# motor-driver.net
KiCad netlist of a schematic drawn in EAGLE
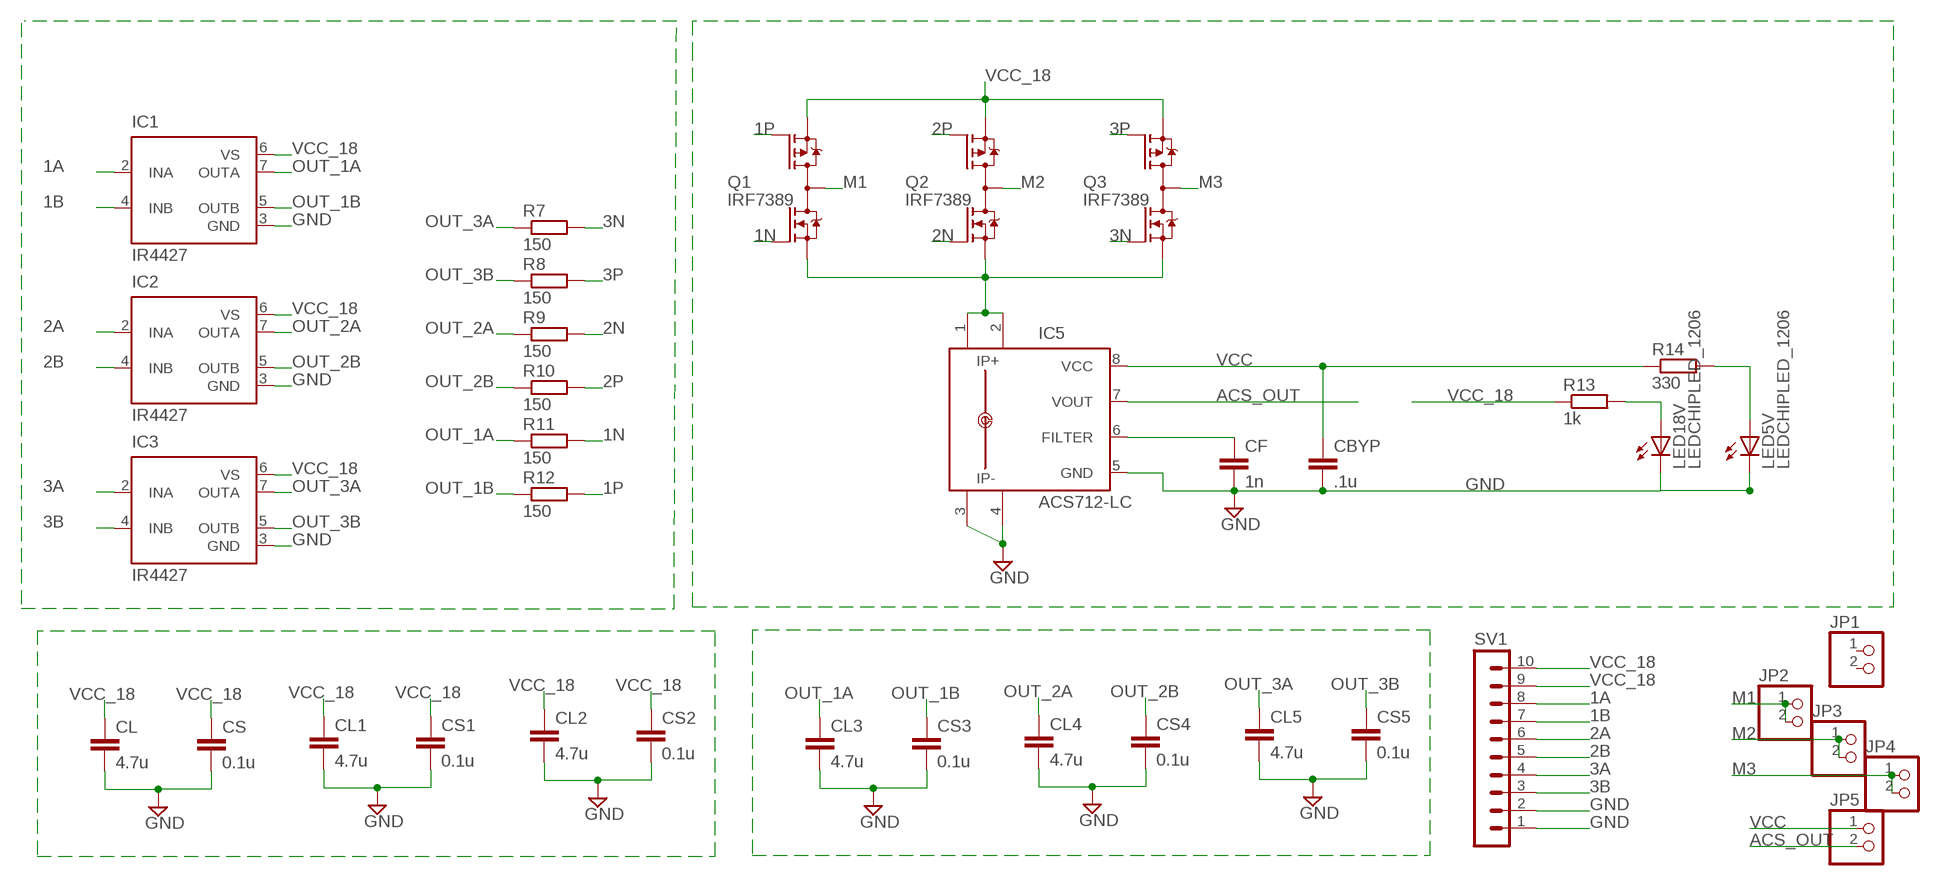
[diagram p0: schematic, sheet 1]

(export (version "E")
  (design (tool "Eeschema 10.0.6"))
  (components
    (comp (ref "CBYP")
      (value ".1u")
      (footprint "eagle-import:C1206")
      (libsource (lib "eagle-import") (part "CC1206"))
    )
    (comp (ref "CF")
      (value "1n")
      (footprint "eagle-import:C1206")
      (libsource (lib "eagle-import") (part "CC1206"))
    )
    (comp (ref "CL")
      (value "4.7u")
      (footprint "eagle-import:C1206")
      (libsource (lib "eagle-import") (part "CC1206"))
    )
    (comp (ref "CL1")
      (value "4.7u")
      (footprint "eagle-import:C1206")
      (libsource (lib "eagle-import") (part "CC1206"))
    )
    (comp (ref "CL2")
      (value "4.7u")
      (footprint "eagle-import:C1206")
      (libsource (lib "eagle-import") (part "CC1206"))
    )
    (comp (ref "CL3")
      (value "4.7u")
      (footprint "eagle-import:C1206")
      (libsource (lib "eagle-import") (part "CC1206"))
    )
    (comp (ref "CL4")
      (value "4.7u")
      (footprint "eagle-import:C1206")
      (libsource (lib "eagle-import") (part "CC1206"))
    )
    (comp (ref "CL5")
      (value "4.7u")
      (footprint "eagle-import:C1206")
      (libsource (lib "eagle-import") (part "CC1206"))
    )
    (comp (ref "CS")
      (value "0.1u")
      (footprint "eagle-import:C1206")
      (libsource (lib "eagle-import") (part "CC1206"))
    )
    (comp (ref "CS1")
      (value "0.1u")
      (footprint "eagle-import:C1206")
      (libsource (lib "eagle-import") (part "CC1206"))
    )
    (comp (ref "CS2")
      (value "0.1u")
      (footprint "eagle-import:C1206")
      (libsource (lib "eagle-import") (part "CC1206"))
    )
    (comp (ref "CS3")
      (value "0.1u")
      (footprint "eagle-import:C1206")
      (libsource (lib "eagle-import") (part "CC1206"))
    )
    (comp (ref "CS4")
      (value "0.1u")
      (footprint "eagle-import:C1206")
      (libsource (lib "eagle-import") (part "CC1206"))
    )
    (comp (ref "CS5")
      (value "0.1u")
      (footprint "eagle-import:C1206")
      (libsource (lib "eagle-import") (part "CC1206"))
    )
    (comp (ref "IC1")
      (value "IR4427")
      (footprint "eagle-import:DIL08")
      (fields (field (name "MF") "INTERNATIONAL RECTIFIER(IR)"))
      (libsource (lib "eagle-import") (part "IR4427"))
    )
    (comp (ref "IC2")
      (value "IR4427")
      (footprint "eagle-import:DIL08")
      (fields (field (name "MF") "INTERNATIONAL RECTIFIER(IR)"))
      (libsource (lib "eagle-import") (part "IR4427"))
    )
    (comp (ref "IC3")
      (value "IR4427")
      (footprint "eagle-import:DIL08")
      (fields (field (name "MF") "INTERNATIONAL RECTIFIER(IR)"))
      (libsource (lib "eagle-import") (part "IR4427"))
    )
    (comp (ref "IC5")
      (value "ACS712-LC")
      (footprint "eagle-import:SOIC8")
      (libsource (lib "eagle-import") (part "ACS712-LC"))
    )
    (comp (ref "JP1")
      (value "PINHD-1X2")
      (footprint "eagle-import:1X02")
      (libsource (lib "eagle-import") (part "PINHD-1X2"))
    )
    (comp (ref "JP2")
      (value "PINHD-1X2")
      (footprint "eagle-import:1X02")
      (libsource (lib "eagle-import") (part "PINHD-1X2"))
    )
    (comp (ref "JP3")
      (value "PINHD-1X2")
      (footprint "eagle-import:1X02")
      (libsource (lib "eagle-import") (part "PINHD-1X2"))
    )
    (comp (ref "JP4")
      (value "PINHD-1X2")
      (footprint "eagle-import:1X02")
      (libsource (lib "eagle-import") (part "PINHD-1X2"))
    )
    (comp (ref "JP5")
      (value "PINHD-1X2")
      (footprint "eagle-import:1X02")
      (libsource (lib "eagle-import") (part "PINHD-1X2"))
    )
    (comp (ref "LED5V")
      (value "LEDCHIPLED_1206")
      (footprint "eagle-import:CHIPLED_1206")
      (libsource (lib "eagle-import") (part "LEDCHIPLED_1206"))
    )
    (comp (ref "LED18V")
      (value "LEDCHIPLED_1206")
      (footprint "eagle-import:CHIPLED_1206")
      (libsource (lib "eagle-import") (part "LEDCHIPLED_1206"))
    )
    (comp (ref "Q1")
      (value "IRF7389")
      (footprint "eagle-import:SO08-IRF")
      (libsource (lib "eagle-import") (part "IRF7389"))
    )
    (comp (ref "Q2")
      (value "IRF7389")
      (footprint "eagle-import:SO08-IRF")
      (libsource (lib "eagle-import") (part "IRF7389"))
    )
    (comp (ref "Q3")
      (value "IRF7389")
      (footprint "eagle-import:SO08-IRF")
      (libsource (lib "eagle-import") (part "IRF7389"))
    )
    (comp (ref "R7")
      (value "150")
      (footprint "eagle-import:R1206")
      (libsource (lib "eagle-import") (part "RR1206"))
    )
    (comp (ref "R8")
      (value "150")
      (footprint "eagle-import:R1206")
      (libsource (lib "eagle-import") (part "RR1206"))
    )
    (comp (ref "R9")
      (value "150")
      (footprint "eagle-import:R1206")
      (libsource (lib "eagle-import") (part "RR1206"))
    )
    (comp (ref "R10")
      (value "150")
      (footprint "eagle-import:R1206")
      (libsource (lib "eagle-import") (part "RR1206"))
    )
    (comp (ref "R11")
      (value "150")
      (footprint "eagle-import:R1206")
      (libsource (lib "eagle-import") (part "RR1206"))
    )
    (comp (ref "R12")
      (value "150")
      (footprint "eagle-import:R1206")
      (libsource (lib "eagle-import") (part "RR1206"))
    )
    (comp (ref "R13")
      (value "1k")
      (footprint "eagle-import:R1206")
      (libsource (lib "eagle-import") (part "RR1206"))
    )
    (comp (ref "R14")
      (value "330")
      (footprint "eagle-import:R1206")
      (libsource (lib "eagle-import") (part "RR1206"))
    )
    (comp (ref "SV1")
      (value "MA10-1")
      (footprint "eagle-import:MA10-1")
      (libsource (lib "eagle-import") (part "MA10-1"))
    )
  )
  (nets
    (net (code "1") (name "/1A") (class "Default")
      (node (ref "IC1") (pin "2") (pinfunction "INA_2") (pintype "input"))
      (node (ref "SV1") (pin "8") (pinfunction "8_8") (pintype "passive"))
    )
    (net (code "2") (name "/1B") (class "Default")
      (node (ref "IC1") (pin "4") (pinfunction "INB_4") (pintype "input"))
      (node (ref "SV1") (pin "7") (pinfunction "7_7") (pintype "passive"))
    )
    (net (code "3") (name "/1N") (class "Default")
      (node (ref "Q1") (pin "2") (pinfunction "N-G_2") (pintype "passive"))
      (node (ref "R11") (pin "2") (pinfunction "2_2") (pintype "passive"))
    )
    (net (code "4") (name "/1P") (class "Default")
      (node (ref "Q1") (pin "4") (pinfunction "P-G_4") (pintype "passive"))
      (node (ref "R12") (pin "2") (pinfunction "2_2") (pintype "passive"))
    )
    (net (code "5") (name "/2A") (class "Default")
      (node (ref "IC2") (pin "2") (pinfunction "INA_2") (pintype "input"))
      (node (ref "SV1") (pin "6") (pinfunction "6_6") (pintype "passive"))
    )
    (net (code "6") (name "/2B") (class "Default")
      (node (ref "IC2") (pin "4") (pinfunction "INB_4") (pintype "input"))
      (node (ref "SV1") (pin "5") (pinfunction "5_5") (pintype "passive"))
    )
    (net (code "7") (name "/2N") (class "Default")
      (node (ref "Q2") (pin "2") (pinfunction "N-G_2") (pintype "passive"))
      (node (ref "R9") (pin "2") (pinfunction "2_2") (pintype "passive"))
    )
    (net (code "8") (name "/2P") (class "Default")
      (node (ref "Q2") (pin "4") (pinfunction "P-G_4") (pintype "passive"))
      (node (ref "R10") (pin "2") (pinfunction "2_2") (pintype "passive"))
    )
    (net (code "9") (name "/3A") (class "Default")
      (node (ref "IC3") (pin "2") (pinfunction "INA_2") (pintype "input"))
      (node (ref "SV1") (pin "4") (pinfunction "4_4") (pintype "passive"))
    )
    (net (code "10") (name "/3B") (class "Default")
      (node (ref "IC3") (pin "4") (pinfunction "INB_4") (pintype "input"))
      (node (ref "SV1") (pin "3") (pinfunction "3_3") (pintype "passive"))
    )
    (net (code "11") (name "/3N") (class "Default")
      (node (ref "Q3") (pin "2") (pinfunction "N-G_2") (pintype "passive"))
      (node (ref "R7") (pin "2") (pinfunction "2_2") (pintype "passive"))
    )
    (net (code "12") (name "/3P") (class "Default")
      (node (ref "Q3") (pin "4") (pinfunction "P-G_4") (pintype "passive"))
      (node (ref "R8") (pin "2") (pinfunction "2_2") (pintype "passive"))
    )
    (net (code "13") (name "/ACS_OUT") (class "Default")
      (node (ref "IC5") (pin "7") (pinfunction "VOUT_7") (pintype "output"))
      (node (ref "JP5") (pin "2") (pinfunction "2_2") (pintype "passive"))
    )
    (net (code "14") (name "/M1") (class "Default")
      (node (ref "JP2") (pin "1") (pinfunction "1_1") (pintype "passive"))
      (node (ref "JP2") (pin "2") (pinfunction "2_2") (pintype "passive"))
      (node (ref "Q1") (pin "5") (pinfunction "D_5") (pintype "passive"))
      (node (ref "Q1") (pin "6") (pinfunction "D_6") (pintype "passive"))
      (node (ref "Q1") (pin "7") (pinfunction "D_7") (pintype "passive"))
      (node (ref "Q1") (pin "8") (pinfunction "D_8") (pintype "passive"))
    )
    (net (code "15") (name "/M2") (class "Default")
      (node (ref "JP3") (pin "1") (pinfunction "1_1") (pintype "passive"))
      (node (ref "JP3") (pin "2") (pinfunction "2_2") (pintype "passive"))
      (node (ref "Q2") (pin "5") (pinfunction "D_5") (pintype "passive"))
      (node (ref "Q2") (pin "6") (pinfunction "D_6") (pintype "passive"))
      (node (ref "Q2") (pin "7") (pinfunction "D_7") (pintype "passive"))
      (node (ref "Q2") (pin "8") (pinfunction "D_8") (pintype "passive"))
    )
    (net (code "16") (name "/M3") (class "Default")
      (node (ref "JP4") (pin "1") (pinfunction "1_1") (pintype "passive"))
      (node (ref "JP4") (pin "2") (pinfunction "2_2") (pintype "passive"))
      (node (ref "Q3") (pin "5") (pinfunction "D_5") (pintype "passive"))
      (node (ref "Q3") (pin "6") (pinfunction "D_6") (pintype "passive"))
      (node (ref "Q3") (pin "7") (pinfunction "D_7") (pintype "passive"))
      (node (ref "Q3") (pin "8") (pinfunction "D_8") (pintype "passive"))
    )
    (net (code "17") (name "/OUT_1A") (class "Default")
      (node (ref "CL3") (pin "1") (pinfunction "1_1") (pintype "passive"))
      (node (ref "IC1") (pin "7") (pinfunction "OUTA_7") (pintype "output"))
      (node (ref "R11") (pin "1") (pinfunction "1_1") (pintype "passive"))
    )
    (net (code "18") (name "/OUT_1B") (class "Default")
      (node (ref "CS3") (pin "1") (pinfunction "1_1") (pintype "passive"))
      (node (ref "IC1") (pin "5") (pinfunction "OUTB_5") (pintype "output"))
      (node (ref "R12") (pin "1") (pinfunction "1_1") (pintype "passive"))
    )
    (net (code "19") (name "/OUT_2A") (class "Default")
      (node (ref "CL4") (pin "1") (pinfunction "1_1") (pintype "passive"))
      (node (ref "IC2") (pin "7") (pinfunction "OUTA_7") (pintype "output"))
      (node (ref "R9") (pin "1") (pinfunction "1_1") (pintype "passive"))
    )
    (net (code "20") (name "/OUT_2B") (class "Default")
      (node (ref "CS4") (pin "1") (pinfunction "1_1") (pintype "passive"))
      (node (ref "IC2") (pin "5") (pinfunction "OUTB_5") (pintype "output"))
      (node (ref "R10") (pin "1") (pinfunction "1_1") (pintype "passive"))
    )
    (net (code "21") (name "/OUT_3A") (class "Default")
      (node (ref "CL5") (pin "1") (pinfunction "1_1") (pintype "passive"))
      (node (ref "IC3") (pin "7") (pinfunction "OUTA_7") (pintype "output"))
      (node (ref "R7") (pin "1") (pinfunction "1_1") (pintype "passive"))
    )
    (net (code "22") (name "/OUT_3B") (class "Default")
      (node (ref "CS5") (pin "1") (pinfunction "1_1") (pintype "passive"))
      (node (ref "IC3") (pin "5") (pinfunction "OUTB_5") (pintype "output"))
      (node (ref "R8") (pin "1") (pinfunction "1_1") (pintype "passive"))
    )
    (net (code "23") (name "/VCC") (class "Default")
      (node (ref "CBYP") (pin "1") (pinfunction "1_1") (pintype "passive"))
      (node (ref "IC5") (pin "8") (pinfunction "VCC_8") (pintype "power_in"))
      (node (ref "JP5") (pin "1") (pinfunction "1_1") (pintype "passive"))
      (node (ref "R14") (pin "1") (pinfunction "1_1") (pintype "passive"))
    )
    (net (code "24") (name "/VCC_18") (class "Default")
      (node (ref "CL") (pin "1") (pinfunction "1_1") (pintype "passive"))
      (node (ref "CL1") (pin "1") (pinfunction "1_1") (pintype "passive"))
      (node (ref "CL2") (pin "1") (pinfunction "1_1") (pintype "passive"))
      (node (ref "CS") (pin "1") (pinfunction "1_1") (pintype "passive"))
      (node (ref "CS1") (pin "1") (pinfunction "1_1") (pintype "passive"))
      (node (ref "CS2") (pin "1") (pinfunction "1_1") (pintype "passive"))
      (node (ref "IC1") (pin "6") (pinfunction "VS_6") (pintype "power_in"))
      (node (ref "IC2") (pin "6") (pinfunction "VS_6") (pintype "power_in"))
      (node (ref "IC3") (pin "6") (pinfunction "VS_6") (pintype "power_in"))
      (node (ref "Q1") (pin "3") (pinfunction "P-S_3") (pintype "passive"))
      (node (ref "Q2") (pin "3") (pinfunction "P-S_3") (pintype "passive"))
      (node (ref "Q3") (pin "3") (pinfunction "P-S_3") (pintype "passive"))
      (node (ref "R13") (pin "1") (pinfunction "1_1") (pintype "passive"))
      (node (ref "SV1") (pin "10") (pinfunction "10_10") (pintype "passive"))
      (node (ref "SV1") (pin "9") (pinfunction "9_9") (pintype "passive"))
    )
    (net (code "25") (name "GND") (class "Default")
      (node (ref "CBYP") (pin "2") (pinfunction "2_2") (pintype "passive"))
      (node (ref "CF") (pin "2") (pinfunction "2_2") (pintype "passive"))
      (node (ref "CL") (pin "2") (pinfunction "2_2") (pintype "passive"))
      (node (ref "CL1") (pin "2") (pinfunction "2_2") (pintype "passive"))
      (node (ref "CL2") (pin "2") (pinfunction "2_2") (pintype "passive"))
      (node (ref "CL3") (pin "2") (pinfunction "2_2") (pintype "passive"))
      (node (ref "CL4") (pin "2") (pinfunction "2_2") (pintype "passive"))
      (node (ref "CL5") (pin "2") (pinfunction "2_2") (pintype "passive"))
      (node (ref "CS") (pin "2") (pinfunction "2_2") (pintype "passive"))
      (node (ref "CS1") (pin "2") (pinfunction "2_2") (pintype "passive"))
      (node (ref "CS2") (pin "2") (pinfunction "2_2") (pintype "passive"))
      (node (ref "CS3") (pin "2") (pinfunction "2_2") (pintype "passive"))
      (node (ref "CS4") (pin "2") (pinfunction "2_2") (pintype "passive"))
      (node (ref "CS5") (pin "2") (pinfunction "2_2") (pintype "passive"))
      (node (ref "IC1") (pin "3") (pinfunction "GND_3") (pintype "power_in"))
      (node (ref "IC2") (pin "3") (pinfunction "GND_3") (pintype "power_in"))
      (node (ref "IC3") (pin "3") (pinfunction "GND_3") (pintype "power_in"))
      (node (ref "IC5") (pin "3") (pinfunction "IP-_3") (pintype "passive"))
      (node (ref "IC5") (pin "4") (pinfunction "IP-1_4") (pintype "passive"))
      (node (ref "IC5") (pin "5") (pinfunction "GND_5") (pintype "power_in"))
      (node (ref "LED18V") (pin "C") (pinfunction "C_C") (pintype "passive"))
      (node (ref "LED5V") (pin "C") (pinfunction "C_C") (pintype "passive"))
      (node (ref "SV1") (pin "1") (pinfunction "1_1") (pintype "passive"))
      (node (ref "SV1") (pin "2") (pinfunction "2_2") (pintype "passive"))
    )
    (net (code "26") (name "Net-(IC5-FILTER)") (class "Default")
      (node (ref "CF") (pin "1") (pinfunction "1_1") (pintype "passive"))
      (node (ref "IC5") (pin "6") (pinfunction "FILTER_6") (pintype "bidirectional"))
    )
    (net (code "27") (name "Net-(IC5-IP+)") (class "Default")
      (node (ref "IC5") (pin "1") (pinfunction "IP+_1") (pintype "passive"))
      (node (ref "IC5") (pin "2") (pinfunction "IP+1_2") (pintype "passive"))
      (node (ref "Q1") (pin "1") (pinfunction "N-S_1") (pintype "passive"))
      (node (ref "Q2") (pin "1") (pinfunction "N-S_1") (pintype "passive"))
      (node (ref "Q3") (pin "1") (pinfunction "N-S_1") (pintype "passive"))
    )
    (net (code "28") (name "Net-(LED5V-PadA)") (class "Default")
      (node (ref "LED5V") (pin "A") (pinfunction "A_A") (pintype "passive"))
      (node (ref "R14") (pin "2") (pinfunction "2_2") (pintype "passive"))
    )
    (net (code "29") (name "Net-(LED18V-PadA)") (class "Default")
      (node (ref "LED18V") (pin "A") (pinfunction "A_A") (pintype "passive"))
      (node (ref "R13") (pin "2") (pinfunction "2_2") (pintype "passive"))
    )
    (net (code "30") (name "unconnected-(JP1-Pad1)") (class "Default")
      (node (ref "JP1") (pin "1") (pinfunction "1_1") (pintype "passive"))
    )
    (net (code "31") (name "unconnected-(JP1-Pad2)") (class "Default")
      (node (ref "JP1") (pin "2") (pinfunction "2_2") (pintype "passive"))
    )
  )
)
